# sensor_node_v1.net
KiCad netlist of a schematic drawn in EAGLE
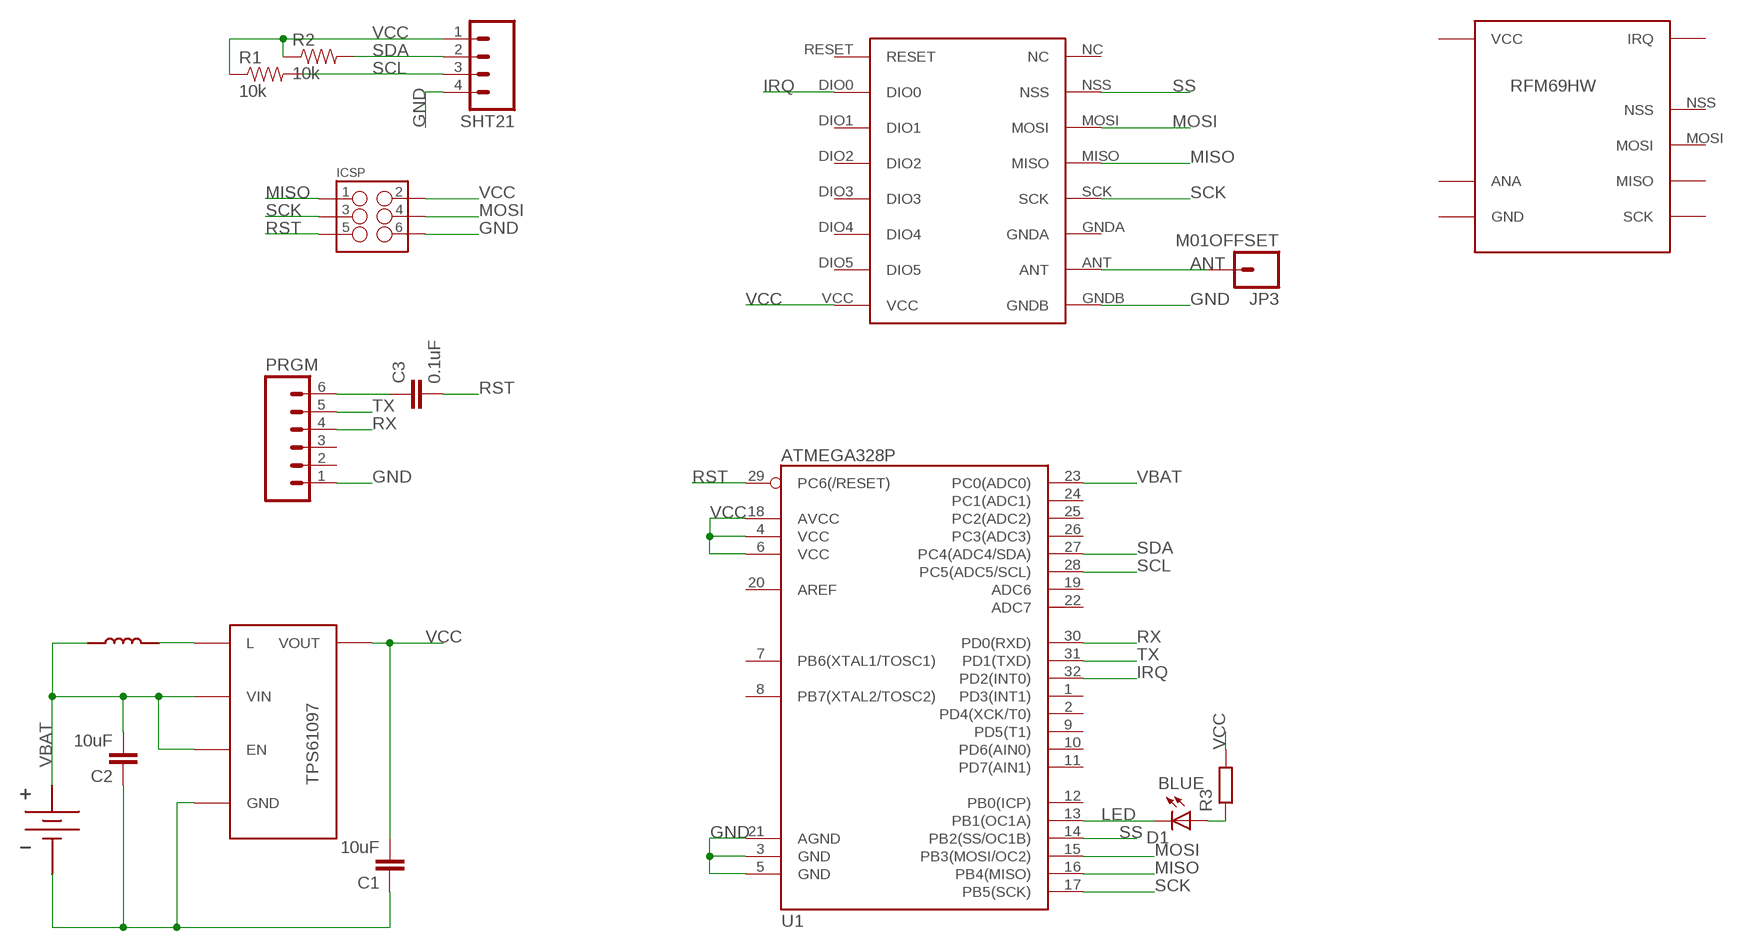
[diagram p0: schematic, sheet 1]

(export (version "E")
  (design (tool "Eeschema 10.0.6"))
  (components
    (comp (ref "C1")
      (value "10uF")
      (footprint "eagle-import:0603-CAP")
      (libsource (lib "eagle-import") (part "10UF-6.3V-20%(0603)"))
    )
    (comp (ref "C2")
      (value "10uF")
      (footprint "eagle-import:0603-CAP")
      (libsource (lib "eagle-import") (part "10UF-6.3V-20%(0603)"))
    )
    (comp (ref "C3")
      (value "0.1uF")
      (footprint "eagle-import:0603-CAP")
      (libsource (lib "eagle-import") (part "0.22UF50V-20%,+80%(0603)"))
    )
    (comp (ref "D1")
      (value "BLUE")
      (footprint "eagle-import:LED-0603")
      (libsource (lib "eagle-import") (part "LED-BLUE0603"))
    )
    (comp (ref "ICSP")
      (value "M03X2FEMALE_SMD")
      (footprint "eagle-import:2X3_SMD")
      (libsource (lib "eagle-import") (part "M03X2FEMALE_SMD"))
    )
    (comp (ref "JP3")
      (value "M01OFFSET")
      (footprint "eagle-import:1X01_OFFSET")
      (libsource (lib "eagle-import") (part "M01OFFSET"))
    )
    (comp (ref "PRGM")
      (value "M06LOCK_LONGPADS")
      (footprint "eagle-import:1X06_LOCK_LONGPADS")
      (libsource (lib "eagle-import") (part "M06LOCK_LONGPADS"))
    )
    (comp (ref "R1")
      (value "10k")
      (footprint "eagle-import:0603-RES")
      (libsource (lib "eagle-import") (part "2.0KOHM1/10W5%(0603)"))
    )
    (comp (ref "R2")
      (value "10k")
      (footprint "eagle-import:0603-RES")
      (libsource (lib "eagle-import") (part "2.0KOHM1/10W5%(0603)"))
    )
    (comp (ref "R3")
      (value "RESISTOR0603-N")
      (footprint "eagle-import:R0603-N")
      (libsource (lib "eagle-import") (part "RESISTOR0603-N"))
    )
    (comp (ref "RFM69HW")
      (value "RFM69HW")
      (footprint "eagle-import:RFM")
      (libsource (lib "eagle-import") (part "RFM69HW"))
    )
    (comp (ref "SHT21")
      (value "M04LOCK_LONGPADS")
      (footprint "eagle-import:1X04_LOCK_LONGPADS")
      (libsource (lib "eagle-import") (part "M04LOCK_LONGPADS"))
    )
    (comp (ref "U$1")
      (value "KEYSTONEAAHOLDER_2CELL")
      (footprint "eagle-import:KEYSTONEAAHOLDER_2CELL")
      (libsource (lib "eagle-import") (part "KEYSTONEAAHOLDER_2CELL"))
    )
    (comp (ref "U$2")
      (value "TPS61097-33")
      (footprint "eagle-import:SOT23-5")
      (libsource (lib "eagle-import") (part "TPS61097-33"))
    )
    (comp (ref "U$3")
      (value "COILCRAFT_DO3314")
      (footprint "eagle-import:COILCRAFT_DO3314")
      (libsource (lib "eagle-import") (part "COILCRAFT_DO3314"))
    )
    (comp (ref "U$4")
      (value "RFM69HW_MIN")
      (footprint "eagle-import:RFM69")
      (libsource (lib "eagle-import") (part "RFM69HW_MIN"))
    )
    (comp (ref "U1")
      (value "ATMEGA328P")
      (footprint "eagle-import:TQFP32-08")
      (libsource (lib "eagle-import") (part "ATMEGA328_SMT"))
    )
  )
  (nets
    (net (code "1") (name "/ANT") (class "Default")
      (node (ref "JP3") (pin "1") (pinfunction "1_1") (pintype "passive"))
      (node (ref "RFM69HW") (pin "ANT") (pinfunction "ANT_ANT") (pintype "bidirectional"))
    )
    (net (code "2") (name "/GND") (class "Default")
      (node (ref "C1") (pin "1") (pinfunction "1_1") (pintype "passive"))
      (node (ref "C2") (pin "1") (pinfunction "1_1") (pintype "passive"))
      (node (ref "ICSP") (pin "6") (pinfunction "6_6") (pintype "bidirectional"))
      (node (ref "PRGM") (pin "1") (pinfunction "1_1") (pintype "passive"))
      (node (ref "RFM69HW") (pin "GNDB") (pinfunction "GNDB_GNDB") (pintype "bidirectional"))
      (node (ref "SHT21") (pin "4") (pinfunction "4_4") (pintype "passive"))
      (node (ref "U$1") (pin "P$2") (pinfunction "GND_P$2") (pintype "bidirectional"))
      (node (ref "U$2") (pin "P$2") (pinfunction "GND_P$2") (pintype "bidirectional"))
      (node (ref "U1") (pin "21") (pinfunction "AGND_21") (pintype "bidirectional"))
      (node (ref "U1") (pin "3") (pinfunction "GND_3") (pintype "bidirectional"))
      (node (ref "U1") (pin "5") (pinfunction "GND_5") (pintype "bidirectional"))
    )
    (net (code "3") (name "/IRQ") (class "Default")
      (node (ref "RFM69HW") (pin "DIO0") (pinfunction "DIO0_DIO0") (pintype "bidirectional"))
      (node (ref "U1") (pin "32") (pinfunction "PD2(INT0)_32") (pintype "bidirectional"))
    )
    (net (code "4") (name "/LED") (class "Default")
      (node (ref "D1") (pin "C") (pinfunction "C_C") (pintype "passive"))
      (node (ref "U1") (pin "13") (pinfunction "PB1(OC1A)_13") (pintype "bidirectional"))
    )
    (net (code "5") (name "/MISO") (class "Default")
      (node (ref "ICSP") (pin "1") (pinfunction "1_1") (pintype "bidirectional"))
      (node (ref "RFM69HW") (pin "MISO") (pinfunction "MISO_MISO") (pintype "bidirectional"))
      (node (ref "U1") (pin "16") (pinfunction "PB4(MISO)_16") (pintype "bidirectional"))
    )
    (net (code "6") (name "/MOSI") (class "Default")
      (node (ref "ICSP") (pin "4") (pinfunction "4_4") (pintype "bidirectional"))
      (node (ref "RFM69HW") (pin "MOSI") (pinfunction "MOSI_MOSI") (pintype "bidirectional"))
      (node (ref "U1") (pin "15") (pinfunction "PB3(MOSI/OC2)_15") (pintype "bidirectional"))
    )
    (net (code "7") (name "/RST") (class "Default")
      (node (ref "C3") (pin "2") (pinfunction "2_2") (pintype "passive"))
      (node (ref "ICSP") (pin "5") (pinfunction "5_5") (pintype "bidirectional"))
      (node (ref "U1") (pin "29") (pinfunction "PC6(/RESET)_29") (pintype "bidirectional"))
    )
    (net (code "8") (name "/RX") (class "Default")
      (node (ref "PRGM") (pin "4") (pinfunction "4_4") (pintype "passive"))
      (node (ref "U1") (pin "30") (pinfunction "PD0(RXD)_30") (pintype "bidirectional"))
    )
    (net (code "9") (name "/SCK") (class "Default")
      (node (ref "ICSP") (pin "3") (pinfunction "3_3") (pintype "bidirectional"))
      (node (ref "RFM69HW") (pin "SCK") (pinfunction "SCK_SCK") (pintype "bidirectional"))
      (node (ref "U1") (pin "17") (pinfunction "PB5(SCK)_17") (pintype "bidirectional"))
    )
    (net (code "10") (name "/SCL") (class "Default")
      (node (ref "R1") (pin "2") (pinfunction "2_2") (pintype "passive"))
      (node (ref "SHT21") (pin "3") (pinfunction "3_3") (pintype "passive"))
      (node (ref "U1") (pin "28") (pinfunction "PC5(ADC5/SCL)_28") (pintype "bidirectional"))
    )
    (net (code "11") (name "/SDA") (class "Default")
      (node (ref "R2") (pin "2") (pinfunction "2_2") (pintype "passive"))
      (node (ref "SHT21") (pin "2") (pinfunction "2_2") (pintype "passive"))
      (node (ref "U1") (pin "27") (pinfunction "PC4(ADC4/SDA)_27") (pintype "bidirectional"))
    )
    (net (code "12") (name "/SS") (class "Default")
      (node (ref "RFM69HW") (pin "NSS") (pinfunction "NSS_NSS") (pintype "bidirectional"))
      (node (ref "U1") (pin "14") (pinfunction "PB2(SS/OC1B)_14") (pintype "bidirectional"))
    )
    (net (code "13") (name "/TX") (class "Default")
      (node (ref "PRGM") (pin "5") (pinfunction "5_5") (pintype "passive"))
      (node (ref "U1") (pin "31") (pinfunction "PD1(TXD)_31") (pintype "bidirectional"))
    )
    (net (code "14") (name "/VBAT") (class "Default")
      (node (ref "C2") (pin "2") (pinfunction "2_2") (pintype "passive"))
      (node (ref "U$1") (pin "P$1") (pinfunction "VBAT_P$1") (pintype "bidirectional"))
      (node (ref "U$2") (pin "P$1") (pinfunction "VIN_P$1") (pintype "bidirectional"))
      (node (ref "U$2") (pin "P$3") (pinfunction "EN_P$3") (pintype "bidirectional"))
      (node (ref "U$3") (pin "P$2") (pinfunction "P$2_P$2") (pintype "bidirectional"))
      (node (ref "U1") (pin "23") (pinfunction "PC0(ADC0)_23") (pintype "bidirectional"))
    )
    (net (code "15") (name "/VCC") (class "Default")
      (node (ref "C1") (pin "2") (pinfunction "2_2") (pintype "passive"))
      (node (ref "ICSP") (pin "2") (pinfunction "2_2") (pintype "bidirectional"))
      (node (ref "R1") (pin "1") (pinfunction "1_1") (pintype "passive"))
      (node (ref "R2") (pin "1") (pinfunction "1_1") (pintype "passive"))
      (node (ref "R3") (pin "2") (pinfunction "P$2_2") (pintype "passive"))
      (node (ref "RFM69HW") (pin "VCC") (pinfunction "VCC_VCC") (pintype "bidirectional"))
      (node (ref "SHT21") (pin "1") (pinfunction "1_1") (pintype "passive"))
      (node (ref "U$2") (pin "P$4") (pinfunction "VOUT_P$4") (pintype "bidirectional"))
      (node (ref "U1") (pin "18") (pinfunction "AVCC_18") (pintype "bidirectional"))
      (node (ref "U1") (pin "4") (pinfunction "VCC_4") (pintype "bidirectional"))
      (node (ref "U1") (pin "6") (pinfunction "VCC_6") (pintype "bidirectional"))
    )
    (net (code "16") (name "Net-(C3-Pad1)") (class "Default")
      (node (ref "C3") (pin "1") (pinfunction "1_1") (pintype "passive"))
      (node (ref "PRGM") (pin "6") (pinfunction "6_6") (pintype "passive"))
    )
    (net (code "17") (name "Net-(R3-P$1)") (class "Default")
      (node (ref "D1") (pin "A") (pinfunction "A_A") (pintype "passive"))
      (node (ref "R3") (pin "1") (pinfunction "P$1_1") (pintype "passive"))
    )
    (net (code "18") (name "Net-(U$2-L)") (class "Default")
      (node (ref "U$2") (pin "P$5") (pinfunction "L_P$5") (pintype "bidirectional"))
      (node (ref "U$3") (pin "P$1") (pinfunction "P$1_P$1") (pintype "bidirectional"))
    )
    (net (code "19") (name "unconnected-(PRGM-Pad2)") (class "Default")
      (node (ref "PRGM") (pin "2") (pinfunction "2_2") (pintype "passive"))
    )
    (net (code "20") (name "unconnected-(PRGM-Pad3)") (class "Default")
      (node (ref "PRGM") (pin "3") (pinfunction "3_3") (pintype "passive"))
    )
    (net (code "21") (name "unconnected-(RFM69HW-PadDIO1)") (class "Default")
      (node (ref "RFM69HW") (pin "DIO1") (pinfunction "DIO1_DIO1") (pintype "bidirectional"))
    )
    (net (code "22") (name "unconnected-(RFM69HW-PadDIO2)") (class "Default")
      (node (ref "RFM69HW") (pin "DIO2") (pinfunction "DIO2_DIO2") (pintype "bidirectional"))
    )
    (net (code "23") (name "unconnected-(RFM69HW-PadDIO3)") (class "Default")
      (node (ref "RFM69HW") (pin "DIO3") (pinfunction "DIO3_DIO3") (pintype "bidirectional"))
    )
    (net (code "24") (name "unconnected-(RFM69HW-PadDIO4)") (class "Default")
      (node (ref "RFM69HW") (pin "DIO4") (pinfunction "DIO4_DIO4") (pintype "bidirectional"))
    )
    (net (code "25") (name "unconnected-(RFM69HW-PadDIO5)") (class "Default")
      (node (ref "RFM69HW") (pin "DIO5") (pinfunction "DIO5_DIO5") (pintype "bidirectional"))
    )
    (net (code "26") (name "unconnected-(RFM69HW-PadGNDA)") (class "Default")
      (node (ref "RFM69HW") (pin "GNDA") (pinfunction "GNDA_GNDA") (pintype "bidirectional"))
    )
    (net (code "27") (name "unconnected-(RFM69HW-PadNC)") (class "Default")
      (node (ref "RFM69HW") (pin "NC") (pinfunction "NC_NC") (pintype "bidirectional"))
    )
    (net (code "28") (name "unconnected-(RFM69HW-PadRESET)") (class "Default")
      (node (ref "RFM69HW") (pin "RESET") (pinfunction "RESET_RESET") (pintype "bidirectional"))
    )
    (net (code "29") (name "unconnected-(U$4-IRQ-PadDIO0)") (class "Default")
      (node (ref "U$4") (pin "DIO0") (pinfunction "IRQ_DIO0") (pintype "bidirectional"))
    )
    (net (code "30") (name "unconnected-(U$4-PadANA)") (class "Default")
      (node (ref "U$4") (pin "ANA") (pinfunction "ANA_ANA") (pintype "bidirectional"))
    )
    (net (code "31") (name "unconnected-(U$4-PadGND)") (class "Default")
      (node (ref "U$4") (pin "GND") (pinfunction "GND_GND") (pintype "bidirectional"))
    )
    (net (code "32") (name "unconnected-(U$4-PadMISO)") (class "Default")
      (node (ref "U$4") (pin "MISO") (pinfunction "MISO_MISO") (pintype "bidirectional"))
    )
    (net (code "33") (name "unconnected-(U$4-PadMOSI)") (class "Default")
      (node (ref "U$4") (pin "MOSI") (pinfunction "MOSI_MOSI") (pintype "bidirectional"))
    )
    (net (code "34") (name "unconnected-(U$4-PadNSS)") (class "Default")
      (node (ref "U$4") (pin "NSS") (pinfunction "NSS_NSS") (pintype "bidirectional"))
    )
    (net (code "35") (name "unconnected-(U$4-PadSCK)") (class "Default")
      (node (ref "U$4") (pin "SCK") (pinfunction "SCK_SCK") (pintype "bidirectional"))
    )
    (net (code "36") (name "unconnected-(U$4-PadVCC)") (class "Default")
      (node (ref "U$4") (pin "VCC") (pinfunction "VCC_VCC") (pintype "bidirectional"))
    )
    (net (code "37") (name "unconnected-(U1-ADC6-Pad19)") (class "Default")
      (node (ref "U1") (pin "19") (pinfunction "ADC6_19") (pintype "bidirectional"))
    )
    (net (code "38") (name "unconnected-(U1-ADC7-Pad22)") (class "Default")
      (node (ref "U1") (pin "22") (pinfunction "ADC7_22") (pintype "bidirectional"))
    )
    (net (code "39") (name "unconnected-(U1-AREF-Pad20)") (class "Default")
      (node (ref "U1") (pin "20") (pinfunction "AREF_20") (pintype "bidirectional"))
    )
    (net (code "40") (name "unconnected-(U1-PB0(ICP)-Pad12)") (class "Default")
      (node (ref "U1") (pin "12") (pinfunction "PB0(ICP)_12") (pintype "bidirectional"))
    )
    (net (code "41") (name "unconnected-(U1-PB6(XTAL1{slash}TOSC1)-Pad7)") (class "Default")
      (node (ref "U1") (pin "7") (pinfunction "PB6(XTAL1/TOSC1)_7") (pintype "bidirectional"))
    )
    (net (code "42") (name "unconnected-(U1-PB7(XTAL2{slash}TOSC2)-Pad8)") (class "Default")
      (node (ref "U1") (pin "8") (pinfunction "PB7(XTAL2/TOSC2)_8") (pintype "bidirectional"))
    )
    (net (code "43") (name "unconnected-(U1-PC1(ADC1)-Pad24)") (class "Default")
      (node (ref "U1") (pin "24") (pinfunction "PC1(ADC1)_24") (pintype "bidirectional"))
    )
    (net (code "44") (name "unconnected-(U1-PC2(ADC2)-Pad25)") (class "Default")
      (node (ref "U1") (pin "25") (pinfunction "PC2(ADC2)_25") (pintype "bidirectional"))
    )
    (net (code "45") (name "unconnected-(U1-PC3(ADC3)-Pad26)") (class "Default")
      (node (ref "U1") (pin "26") (pinfunction "PC3(ADC3)_26") (pintype "bidirectional"))
    )
    (net (code "46") (name "unconnected-(U1-PD3(INT1)-Pad1)") (class "Default")
      (node (ref "U1") (pin "1") (pinfunction "PD3(INT1)_1") (pintype "bidirectional"))
    )
    (net (code "47") (name "unconnected-(U1-PD4(XCK{slash}T0)-Pad2)") (class "Default")
      (node (ref "U1") (pin "2") (pinfunction "PD4(XCK/T0)_2") (pintype "bidirectional"))
    )
    (net (code "48") (name "unconnected-(U1-PD5(T1)-Pad9)") (class "Default")
      (node (ref "U1") (pin "9") (pinfunction "PD5(T1)_9") (pintype "bidirectional"))
    )
    (net (code "49") (name "unconnected-(U1-PD6(AIN0)-Pad10)") (class "Default")
      (node (ref "U1") (pin "10") (pinfunction "PD6(AIN0)_10") (pintype "bidirectional"))
    )
    (net (code "50") (name "unconnected-(U1-PD7(AIN1)-Pad11)") (class "Default")
      (node (ref "U1") (pin "11") (pinfunction "PD7(AIN1)_11") (pintype "bidirectional"))
    )
  )
)
